# SCH_meshkey.net
KiCad netlist of a schematic drawn in EasyEDA
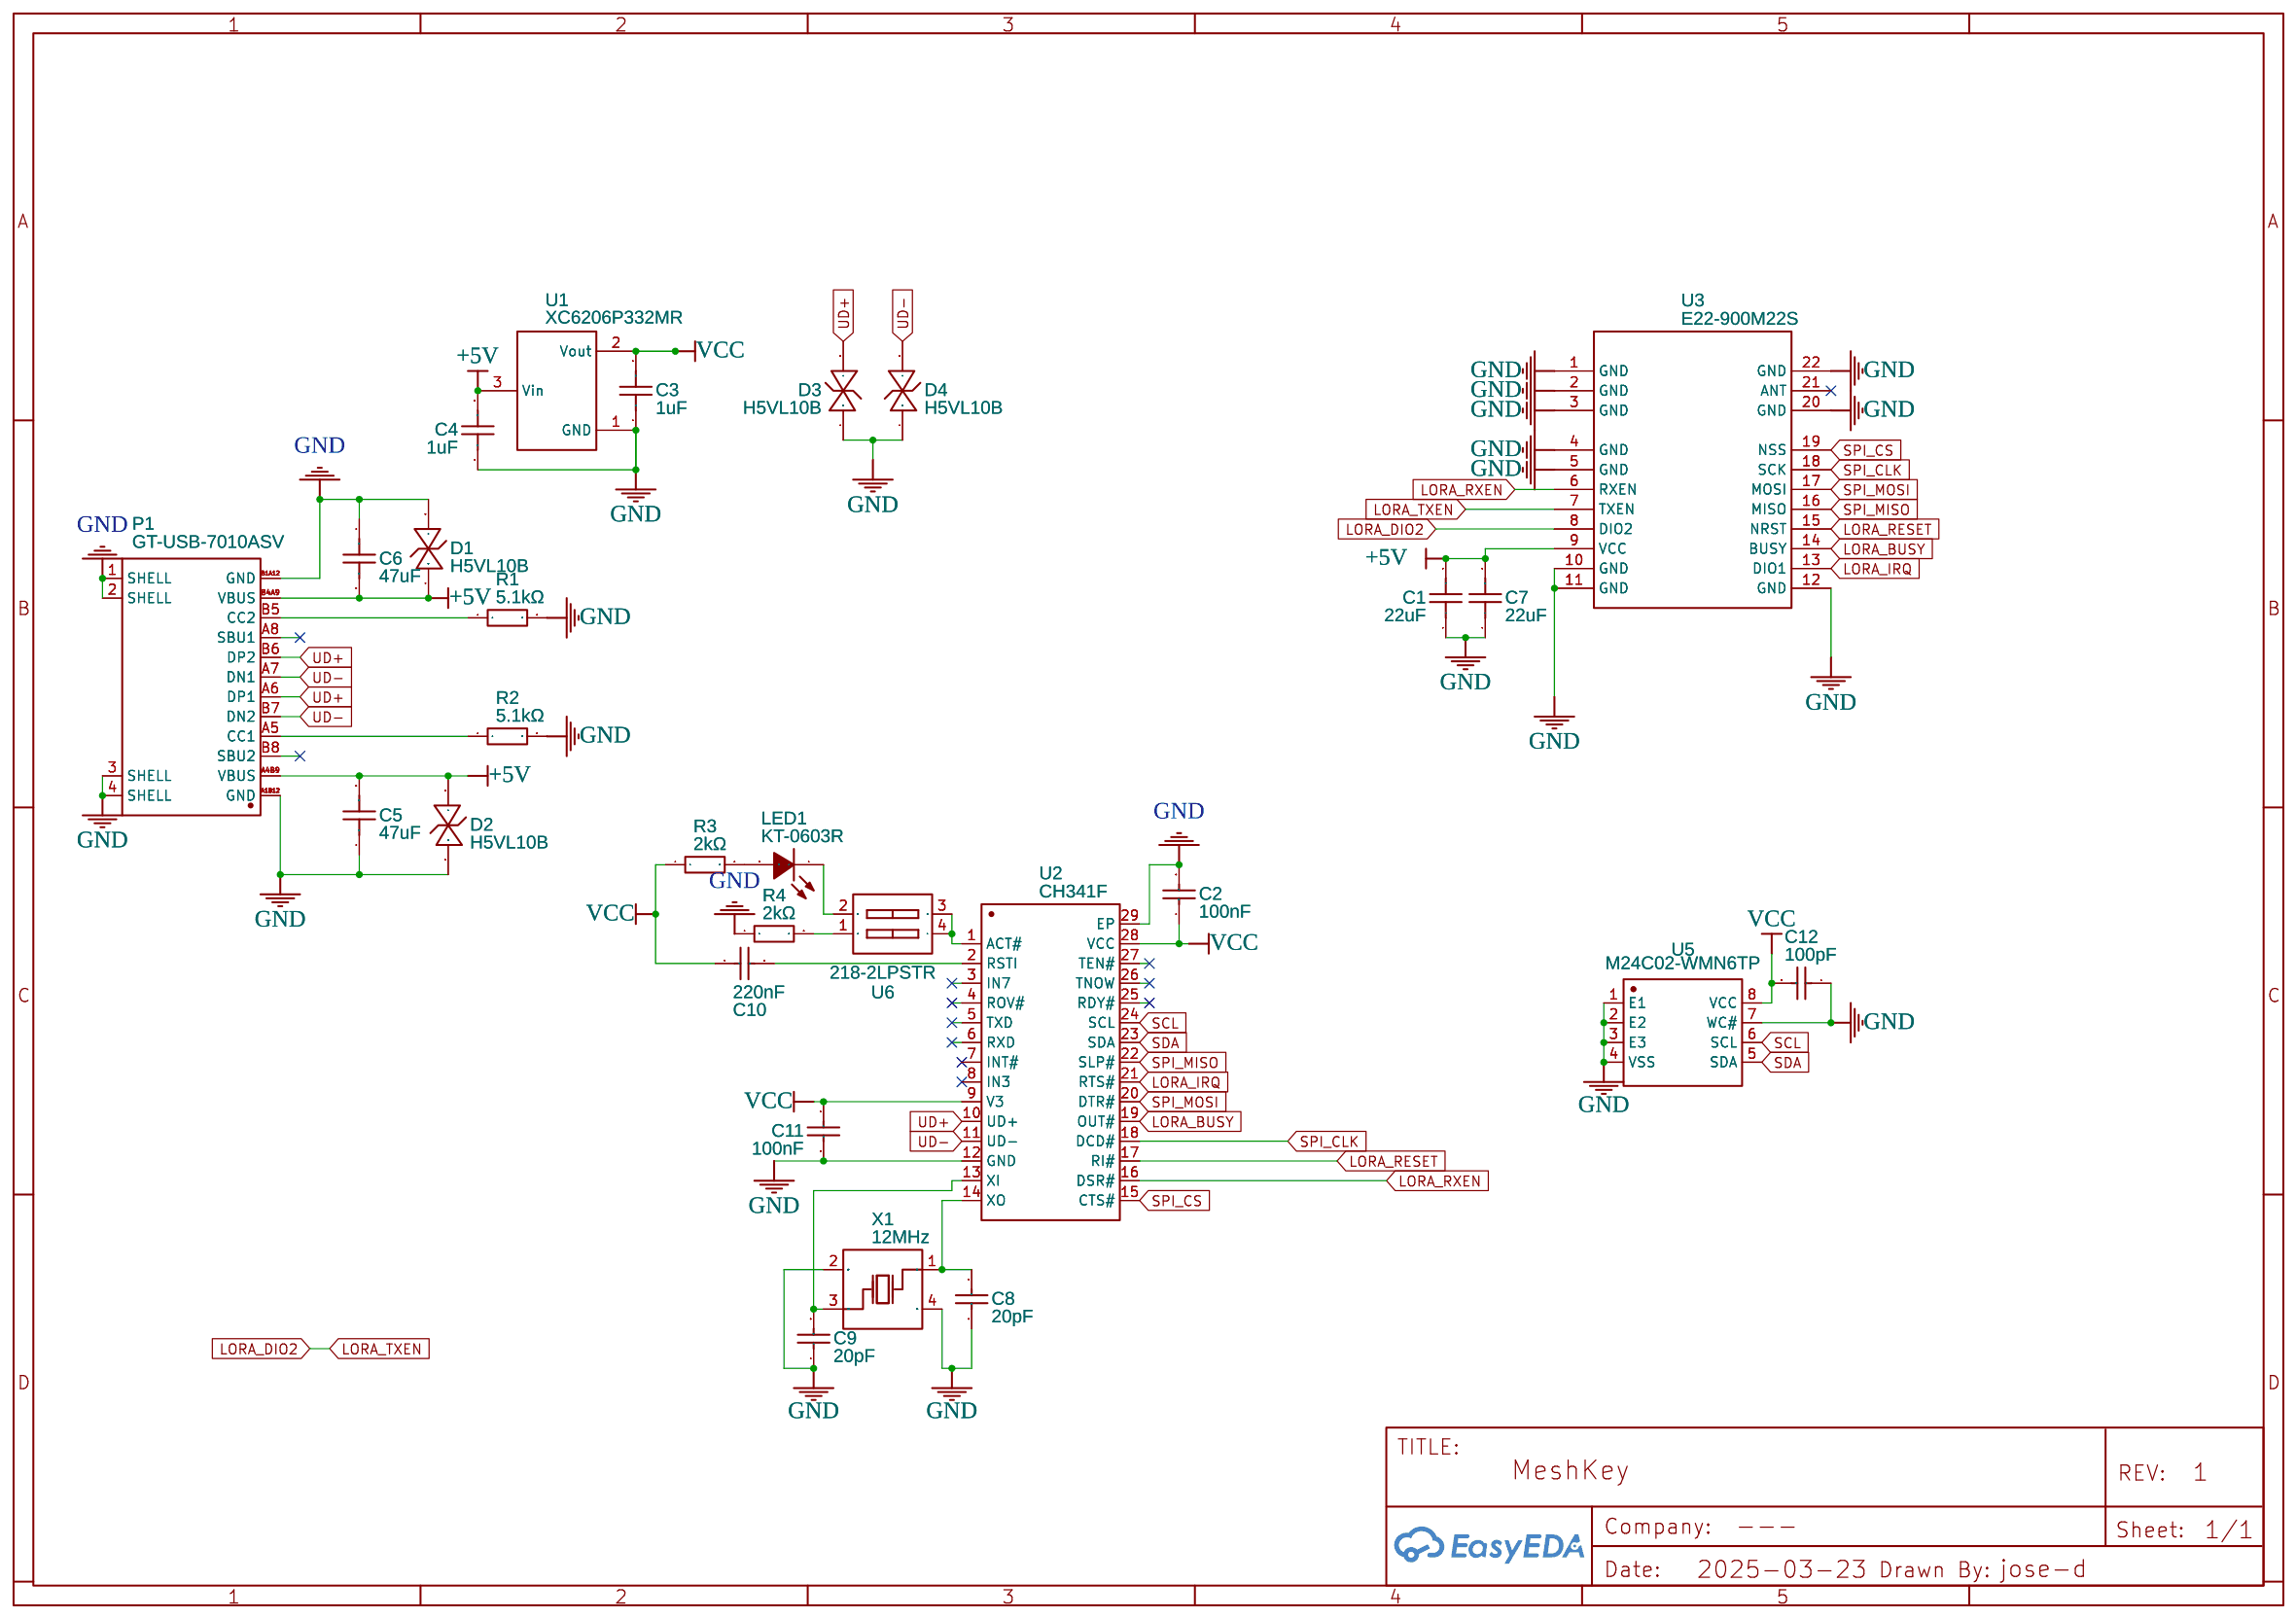
[diagram p0: schematic sheet]

(export (version "E")
  (design (tool "Eeschema 10.0.6"))
  (components
    (comp (ref "C1")
      (value "22uF")
      (fields
        (field (name "Manufacturer Part") "CL21A226MAQNNNE")
        (field (name "Manufacturer") "SAMSUNG(三星)")
      )
      (libsource (lib "") (part "CL21A226MAQNNNE_1"))
    )
    (comp (ref "C2")
      (value "100nF")
      (fields (field (name "Manufacturer Part") "CL05B104KO5NNNC") (field (name "Manufacturer") "FH(风华)"))
      (libsource (lib "") (part "0402CG101J500NT_2"))
    )
    (comp (ref "C3")
      (value "1uF")
      (fields
        (field (name "Manufacturer Part") "CL10A105KB8NNNC")
        (field (name "Manufacturer") "SAMSUNG(三星)")
      )
      (libsource (lib "") (part "CL10A105KB8NNNC_1"))
    )
    (comp (ref "C4")
      (value "1uF")
      (fields
        (field (name "Manufacturer Part") "CL10A105KB8NNNC")
        (field (name "Manufacturer") "SAMSUNG(三星)")
      )
      (libsource (lib "") (part "CL10A105KB8NNNC"))
    )
    (comp (ref "C5")
      (value "47uF")
      (fields
        (field (name "Manufacturer Part") "CL31A476MPHNNNE")
        (field (name "Manufacturer") "SAMSUNG(三星)")
      )
      (libsource (lib "") (part "CL31A476MPHNNNE_1"))
    )
    (comp (ref "C6")
      (value "47uF")
      (fields
        (field (name "Manufacturer Part") "CL31A476MPHNNNE")
        (field (name "Manufacturer") "SAMSUNG(三星)")
      )
      (libsource (lib "") (part "CL31A476MPHNNNE"))
    )
    (comp (ref "C7")
      (value "22uF")
      (fields
        (field (name "Manufacturer Part") "CL21A226MAQNNNE")
        (field (name "Manufacturer") "SAMSUNG(三星)")
      )
      (libsource (lib "") (part "CL21A226MAQNNNE"))
    )
    (comp (ref "C8")
      (value "20pF")
      (fields (field (name "Manufacturer Part") "0402CG200J500NT") (field (name "Manufacturer") "FH(风华)"))
      (libsource (lib "") (part "0402CG200J500NT"))
    )
    (comp (ref "C9")
      (value "20pF")
      (fields (field (name "Manufacturer Part") "0402CG200J500NT") (field (name "Manufacturer") "FH(风华)"))
      (libsource (lib "") (part "0402CG200J500NT_1"))
    )
    (comp (ref "C10")
      (value "220nF")
      (fields (field (name "Manufacturer Part") "CL05B224KO5NNNC") (field (name "Manufacturer") "FH(风华)"))
      (libsource (lib "") (part "0402B471K500NT"))
    )
    (comp (ref "C11")
      (value "100nF")
      (fields (field (name "Manufacturer Part") "CL05B104KO5NNNC") (field (name "Manufacturer") "FH(风华)"))
      (libsource (lib "") (part "0402CG101J500NT_1"))
    )
    (comp (ref "C12")
      (value "100pF")
      (fields (field (name "Manufacturer Part") "CL05B104KO5NNNC") (field (name "Manufacturer") "FH(风华)"))
      (libsource (lib "") (part "0402CG101J500NT"))
    )
    (comp (ref "D1")
      (value "H5VL10B")
      (fields (field (name "Manufacturer") "宏迦橙"))
      (libsource (lib "") (part "H5VL10B_1"))
    )
    (comp (ref "D2")
      (value "H5VL10B")
      (fields (field (name "Manufacturer") "宏迦橙"))
      (libsource (lib "") (part "H5VL10B_1"))
    )
    (comp (ref "D3")
      (value "H5VL10B")
      (fields (field (name "Manufacturer") "宏迦橙"))
      (libsource (lib "") (part "H5VL10B"))
    )
    (comp (ref "D4")
      (value "H5VL10B")
      (fields (field (name "Manufacturer") "宏迦橙"))
      (libsource (lib "") (part "H5VL10B_1"))
    )
    (comp (ref "LED1")
      (value "KT-0603R")
      (fields (field (name "Manufacturer") "KENTO"))
      (libsource (lib "") (part "KT-0603R"))
    )
    (comp (ref "P1")
      (value "GT-USB-7010ASV")
      (fields (field (name "Manufacturer") "G-Switch(品赞)"))
      (libsource (lib "") (part "GT-USB-7010ASV"))
    )
    (comp (ref "R1")
      (value "5.1kΩ")
      (fields
        (field (name "Manufacturer Part") "0402WGF5101TCE")
        (field (name "Manufacturer") "UNI-ROYAL(厚声)")
      )
      (libsource (lib "") (part "0402WGF5101TCE"))
    )
    (comp (ref "R2")
      (value "5.1kΩ")
      (fields
        (field (name "Manufacturer Part") "0402WGF5101TCE")
        (field (name "Manufacturer") "UNI-ROYAL(厚声)")
      )
      (libsource (lib "") (part "0402WGF5101TCE"))
    )
    (comp (ref "R3")
      (value "2kΩ")
      (fields
        (field (name "Manufacturer Part") "0402WGF2001TCE")
        (field (name "Manufacturer") "UNI-ROYAL(厚声)")
      )
      (libsource (lib "") (part "0402WGF2001TCE"))
    )
    (comp (ref "R4")
      (value "2kΩ")
      (fields
        (field (name "Manufacturer Part") "0402WGF2001TCE")
        (field (name "Manufacturer") "UNI-ROYAL(厚声)")
      )
      (libsource (lib "") (part "0402WGF2001TCE"))
    )
    (comp (ref "U1")
      (value "XC6206P332MR")
      (fields (field (name "Manufacturer Part") "XC6206P332MR-G") (field (name "Manufacturer") "TOREX(特瑞仕)"))
      (libsource (lib "") (part "XC6206P332MR"))
    )
    (comp (ref "U2")
      (value "CH341F")
      (fields (field (name "Manufacturer") "WCH(南京沁恒)"))
      (libsource (lib "") (part "CH341F"))
    )
    (comp (ref "U3")
      (value "E22-900M22S")
      (fields (field (name "Manufacturer") "EBYTE(亿佰特)"))
      (libsource (lib "") (part "E22-900M22S"))
    )
    (comp (ref "U5")
      (value "M24C02-WMN6TP")
      (fields (field (name "Manufacturer") "ST(意法半导体)"))
      (libsource (lib "") (part "M24C02-WMN6TP"))
    )
    (comp (ref "U6")
      (value "218-2LPSTR")
      (fields (field (name "Manufacturer") "CTS(西迪斯)"))
      (libsource (lib "") (part "218-2LPSTR"))
    )
    (comp (ref "X1")
      (value "12MHz")
      (fields (field (name "Manufacturer Part") "X322512MSB4SI") (field (name "Manufacturer") "YXC(扬兴晶振)"))
      (libsource (lib "") (part "X322512MSB4SI"))
    )
  )
  (nets
    (net (code "1") (name "+5V") (class "Default")
      (node (ref "C1") (pin "2") (pinfunction "2_2") (pintype "unspecified"))
      (node (ref "C4") (pin "2") (pinfunction "2_2") (pintype "unspecified"))
      (node (ref "C5") (pin "2") (pinfunction "2_2") (pintype "unspecified"))
      (node (ref "C6") (pin "2") (pinfunction "2_2") (pintype "unspecified"))
      (node (ref "C7") (pin "2") (pinfunction "2_2") (pintype "unspecified"))
      (node (ref "D1") (pin "1") (pinfunction "C_1") (pintype "unspecified"))
      (node (ref "D2") (pin "2") (pinfunction "A_2") (pintype "unspecified"))
      (node (ref "P1") (pin "A4B9") (pinfunction "VBUS_A4B9") (pintype "unspecified"))
      (node (ref "P1") (pin "B4A9") (pinfunction "VBUS_B4A9") (pintype "unspecified"))
      (node (ref "U1") (pin "3") (pinfunction "Vin_3") (pintype "unspecified"))
      (node (ref "U3") (pin "9") (pinfunction "VCC_9") (pintype "unspecified"))
    )
    (net (code "2") (name "GND") (class "Default")
      (node (ref "C1") (pin "1") (pinfunction "1_1") (pintype "unspecified"))
      (node (ref "C11") (pin "2") (pinfunction "2_2") (pintype "input"))
      (node (ref "C12") (pin "1") (pinfunction "1_1") (pintype "input"))
      (node (ref "C2") (pin "2") (pinfunction "2_2") (pintype "input"))
      (node (ref "C3") (pin "1") (pinfunction "1_1") (pintype "unspecified"))
      (node (ref "C4") (pin "1") (pinfunction "1_1") (pintype "unspecified"))
      (node (ref "C5") (pin "1") (pinfunction "1_1") (pintype "unspecified"))
      (node (ref "C6") (pin "1") (pinfunction "1_1") (pintype "unspecified"))
      (node (ref "C7") (pin "1") (pinfunction "1_1") (pintype "unspecified"))
      (node (ref "C8") (pin "2") (pinfunction "2_2") (pintype "input"))
      (node (ref "C9") (pin "1") (pinfunction "1_1") (pintype "input"))
      (node (ref "D1") (pin "2") (pinfunction "A_2") (pintype "unspecified"))
      (node (ref "D2") (pin "1") (pinfunction "C_1") (pintype "unspecified"))
      (node (ref "D3") (pin "1") (pinfunction "C_1") (pintype "unspecified"))
      (node (ref "D4") (pin "1") (pinfunction "C_1") (pintype "unspecified"))
      (node (ref "P1") (pin "1") (pinfunction "SHELL_1") (pintype "unspecified"))
      (node (ref "P1") (pin "2") (pinfunction "SHELL_2") (pintype "unspecified"))
      (node (ref "P1") (pin "3") (pinfunction "SHELL_3") (pintype "unspecified"))
      (node (ref "P1") (pin "4") (pinfunction "SHELL_4") (pintype "unspecified"))
      (node (ref "P1") (pin "A1B12") (pinfunction "GND_A1B12") (pintype "unspecified"))
      (node (ref "P1") (pin "B1A12") (pinfunction "GND_B1A12") (pintype "unspecified"))
      (node (ref "R1") (pin "2") (pinfunction "2_2") (pintype "input"))
      (node (ref "R2") (pin "2") (pinfunction "2_2") (pintype "input"))
      (node (ref "R4") (pin "1") (pinfunction "1_1") (pintype "input"))
      (node (ref "U1") (pin "1") (pinfunction "GND_1") (pintype "unspecified"))
      (node (ref "U2") (pin "12") (pinfunction "GND_12") (pintype "unspecified"))
      (node (ref "U2") (pin "29") (pinfunction "EP_29") (pintype "unspecified"))
      (node (ref "U3") (pin "1") (pinfunction "GND_1") (pintype "unspecified"))
      (node (ref "U3") (pin "10") (pinfunction "GND_10") (pintype "unspecified"))
      (node (ref "U3") (pin "11") (pinfunction "GND_11") (pintype "unspecified"))
      (node (ref "U3") (pin "12") (pinfunction "GND_12") (pintype "unspecified"))
      (node (ref "U3") (pin "2") (pinfunction "GND_2") (pintype "unspecified"))
      (node (ref "U3") (pin "20") (pinfunction "GND_20") (pintype "unspecified"))
      (node (ref "U3") (pin "22") (pinfunction "GND_22") (pintype "unspecified"))
      (node (ref "U3") (pin "3") (pinfunction "GND_3") (pintype "unspecified"))
      (node (ref "U3") (pin "4") (pinfunction "GND_4") (pintype "unspecified"))
      (node (ref "U3") (pin "5") (pinfunction "GND_5") (pintype "unspecified"))
      (node (ref "U5") (pin "1") (pinfunction "E1_1") (pintype "unspecified"))
      (node (ref "U5") (pin "2") (pinfunction "E2_2") (pintype "unspecified"))
      (node (ref "U5") (pin "3") (pinfunction "E3_3") (pintype "unspecified"))
      (node (ref "U5") (pin "4") (pinfunction "VSS_4") (pintype "unspecified"))
      (node (ref "U5") (pin "7") (pinfunction "WC#_7") (pintype "unspecified"))
      (node (ref "X1") (pin "2") (pinfunction "GND_2") (pintype "unspecified"))
      (node (ref "X1") (pin "4") (pinfunction "GND_4") (pintype "unspecified"))
    )
    (net (code "3") (name "LORA_BUSY") (class "Default")
      (node (ref "U2") (pin "19") (pinfunction "OUT#_19") (pintype "unspecified"))
      (node (ref "U3") (pin "14") (pinfunction "BUSY_14") (pintype "unspecified"))
    )
    (net (code "4") (name "LORA_DIO2") (class "Default")
      (node (ref "U3") (pin "7") (pinfunction "TXEN_7") (pintype "unspecified"))
      (node (ref "U3") (pin "8") (pinfunction "DIO2_8") (pintype "unspecified"))
    )
    (net (code "5") (name "LORA_IRQ") (class "Default")
      (node (ref "U2") (pin "21") (pinfunction "RTS#_21") (pintype "unspecified"))
      (node (ref "U3") (pin "13") (pinfunction "DIO1_13") (pintype "unspecified"))
    )
    (net (code "6") (name "LORA_RESET") (class "Default")
      (node (ref "U2") (pin "17") (pinfunction "RI#_17") (pintype "unspecified"))
      (node (ref "U3") (pin "15") (pinfunction "NRST_15") (pintype "unspecified"))
    )
    (net (code "7") (name "LORA_RXEN") (class "Default")
      (node (ref "U2") (pin "16") (pinfunction "DSR#_16") (pintype "unspecified"))
      (node (ref "U3") (pin "6") (pinfunction "RXEN_6") (pintype "unspecified"))
    )
    (net (code "8") (name "Net-(LED1-A)") (class "Default")
      (node (ref "LED1") (pin "2") (pinfunction "A_2") (pintype "unspecified"))
      (node (ref "R3") (pin "2") (pinfunction "2_2") (pintype "input"))
    )
    (net (code "9") (name "Net-(LED1-K)") (class "Default")
      (node (ref "LED1") (pin "1") (pinfunction "K_1") (pintype "unspecified"))
      (node (ref "U6") (pin "2") (pinfunction "2_2") (pintype "input"))
    )
    (net (code "10") (name "Net-(P1-CC1)") (class "Default")
      (node (ref "P1") (pin "A5") (pinfunction "CC1_A5") (pintype "unspecified"))
      (node (ref "R2") (pin "1") (pinfunction "1_1") (pintype "input"))
    )
    (net (code "11") (name "Net-(P1-CC2)") (class "Default")
      (node (ref "P1") (pin "B5") (pinfunction "CC2_B5") (pintype "unspecified"))
      (node (ref "R1") (pin "1") (pinfunction "1_1") (pintype "input"))
    )
    (net (code "12") (name "Net-(R4-Pad2)") (class "Default")
      (node (ref "R4") (pin "2") (pinfunction "2_2") (pintype "input"))
      (node (ref "U6") (pin "1") (pinfunction "1_1") (pintype "input"))
    )
    (net (code "13") (name "Net-(U2-ACT#)") (class "Default")
      (node (ref "U2") (pin "1") (pinfunction "ACT#_1") (pintype "unspecified"))
      (node (ref "U6") (pin "3") (pinfunction "3_3") (pintype "input"))
      (node (ref "U6") (pin "4") (pinfunction "4_4") (pintype "input"))
    )
    (net (code "14") (name "Net-(U2-RSTI)") (class "Default")
      (node (ref "C10") (pin "2") (pinfunction "2_2") (pintype "input"))
      (node (ref "U2") (pin "2") (pinfunction "RSTI_2") (pintype "unspecified"))
    )
    (net (code "15") (name "Net-(U2-XI)") (class "Default")
      (node (ref "C9") (pin "2") (pinfunction "2_2") (pintype "input"))
      (node (ref "U2") (pin "13") (pinfunction "XI_13") (pintype "unspecified"))
      (node (ref "X1") (pin "3") (pinfunction "OSC2_3") (pintype "unspecified"))
    )
    (net (code "16") (name "Net-(U2-XO)") (class "Default")
      (node (ref "C8") (pin "1") (pinfunction "1_1") (pintype "input"))
      (node (ref "U2") (pin "14") (pinfunction "XO_14") (pintype "unspecified"))
      (node (ref "X1") (pin "1") (pinfunction "OSC1_1") (pintype "unspecified"))
    )
    (net (code "17") (name "SCL") (class "Default")
      (node (ref "U2") (pin "24") (pinfunction "SCL_24") (pintype "unspecified"))
      (node (ref "U5") (pin "6") (pinfunction "SCL_6") (pintype "unspecified"))
    )
    (net (code "18") (name "SDA") (class "Default")
      (node (ref "U2") (pin "23") (pinfunction "SDA_23") (pintype "unspecified"))
      (node (ref "U5") (pin "5") (pinfunction "SDA_5") (pintype "unspecified"))
    )
    (net (code "19") (name "SPI_CLK") (class "Default")
      (node (ref "U2") (pin "18") (pinfunction "DCD#_18") (pintype "unspecified"))
      (node (ref "U3") (pin "18") (pinfunction "SCK_18") (pintype "unspecified"))
    )
    (net (code "20") (name "SPI_CS") (class "Default")
      (node (ref "U2") (pin "15") (pinfunction "CTS#_15") (pintype "unspecified"))
      (node (ref "U3") (pin "19") (pinfunction "NSS_19") (pintype "unspecified"))
    )
    (net (code "21") (name "SPI_MISO") (class "Default")
      (node (ref "U2") (pin "22") (pinfunction "SLP#_22") (pintype "unspecified"))
      (node (ref "U3") (pin "16") (pinfunction "MISO_16") (pintype "unspecified"))
    )
    (net (code "22") (name "SPI_MOSI") (class "Default")
      (node (ref "U2") (pin "20") (pinfunction "DTR#_20") (pintype "unspecified"))
      (node (ref "U3") (pin "17") (pinfunction "MOSI_17") (pintype "unspecified"))
    )
    (net (code "23") (name "UD+") (class "Default")
      (node (ref "D3") (pin "2") (pinfunction "A_2") (pintype "unspecified"))
      (node (ref "P1") (pin "A6") (pinfunction "DP1_A6") (pintype "unspecified"))
      (node (ref "P1") (pin "B6") (pinfunction "DP2_B6") (pintype "unspecified"))
      (node (ref "U2") (pin "10") (pinfunction "UD+_10") (pintype "unspecified"))
    )
    (net (code "24") (name "UD-") (class "Default")
      (node (ref "D4") (pin "2") (pinfunction "A_2") (pintype "unspecified"))
      (node (ref "P1") (pin "A7") (pinfunction "DN1_A7") (pintype "unspecified"))
      (node (ref "P1") (pin "B7") (pinfunction "DN2_B7") (pintype "unspecified"))
      (node (ref "U2") (pin "11") (pinfunction "UD-_11") (pintype "unspecified"))
    )
    (net (code "25") (name "VCC") (class "Default")
      (node (ref "C10") (pin "1") (pinfunction "1_1") (pintype "input"))
      (node (ref "C11") (pin "1") (pinfunction "1_1") (pintype "input"))
      (node (ref "C12") (pin "2") (pinfunction "2_2") (pintype "input"))
      (node (ref "C2") (pin "1") (pinfunction "1_1") (pintype "input"))
      (node (ref "C3") (pin "2") (pinfunction "2_2") (pintype "unspecified"))
      (node (ref "R3") (pin "1") (pinfunction "1_1") (pintype "input"))
      (node (ref "U1") (pin "2") (pinfunction "Vout_2") (pintype "unspecified"))
      (node (ref "U2") (pin "28") (pinfunction "VCC_28") (pintype "unspecified"))
      (node (ref "U2") (pin "9") (pinfunction "V3_9") (pintype "unspecified"))
      (node (ref "U5") (pin "8") (pinfunction "VCC_8") (pintype "unspecified"))
    )
    (net (code "26") (name "unconnected-(P1-SBU1-PadA8)") (class "Default")
      (node (ref "P1") (pin "A8") (pinfunction "SBU1_A8") (pintype "unspecified+no_connect"))
    )
    (net (code "27") (name "unconnected-(P1-SBU2-PadB8)") (class "Default")
      (node (ref "P1") (pin "B8") (pinfunction "SBU2_B8") (pintype "unspecified+no_connect"))
    )
    (net (code "28") (name "unconnected-(U2-IN3-Pad8)") (class "Default")
      (node (ref "U2") (pin "8") (pinfunction "IN3_8") (pintype "unspecified+no_connect"))
    )
    (net (code "29") (name "unconnected-(U2-IN7-Pad3)") (class "Default")
      (node (ref "U2") (pin "3") (pinfunction "IN7_3") (pintype "unspecified+no_connect"))
    )
    (net (code "30") (name "unconnected-(U2-INT#-Pad7)") (class "Default")
      (node (ref "U2") (pin "7") (pinfunction "INT#_7") (pintype "unspecified+no_connect"))
    )
    (net (code "31") (name "unconnected-(U2-RDY#-Pad25)") (class "Default")
      (node (ref "U2") (pin "25") (pinfunction "RDY#_25") (pintype "unspecified+no_connect"))
    )
    (net (code "32") (name "unconnected-(U2-ROV#-Pad4)") (class "Default")
      (node (ref "U2") (pin "4") (pinfunction "ROV#_4") (pintype "unspecified+no_connect"))
    )
    (net (code "33") (name "unconnected-(U2-RXD-Pad6)") (class "Default")
      (node (ref "U2") (pin "6") (pinfunction "RXD_6") (pintype "unspecified+no_connect"))
    )
    (net (code "34") (name "unconnected-(U2-TEN#-Pad27)") (class "Default")
      (node (ref "U2") (pin "27") (pinfunction "TEN#_27") (pintype "unspecified+no_connect"))
    )
    (net (code "35") (name "unconnected-(U2-TNOW-Pad26)") (class "Default")
      (node (ref "U2") (pin "26") (pinfunction "TNOW_26") (pintype "unspecified+no_connect"))
    )
    (net (code "36") (name "unconnected-(U2-TXD-Pad5)") (class "Default")
      (node (ref "U2") (pin "5") (pinfunction "TXD_5") (pintype "unspecified+no_connect"))
    )
    (net (code "37") (name "unconnected-(U3-ANT-Pad21)") (class "Default")
      (node (ref "U3") (pin "21") (pinfunction "ANT_21") (pintype "unspecified+no_connect"))
    )
  )
)
